# Instruction_Register_Electronic_Scheme_2.net
KiCad netlist of a schematic drawn in Altium Designer
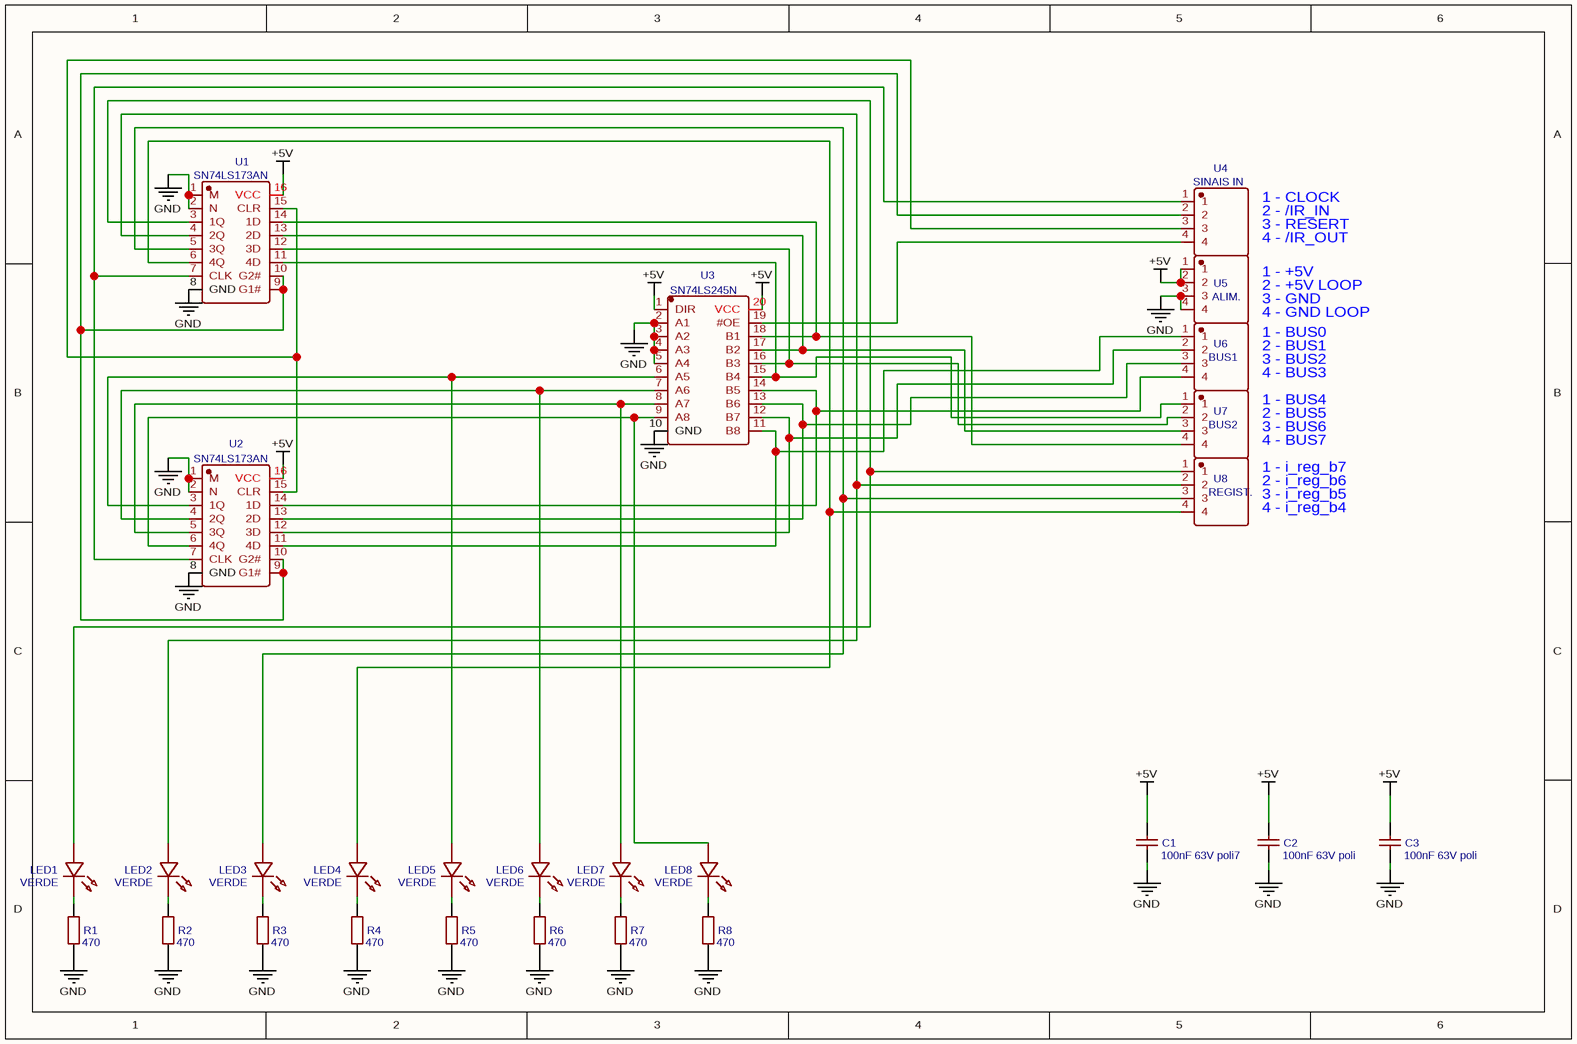
[diagram p0: Instruction Register Electronic Scheme_2021-10-21.schdoc]

(export (version "E")
  (design (tool "Eeschema 10.0.6"))
  (components
    (comp (ref "C1")
      (value "100nF 63V poli7")
      (fields
        (field (name "BOM_SUPPLIER PART") "C444741")
        (field (name "BOM_MANUFACTURER PART") "SR305C105KAR")
        (field (name "CONTRIBUTOR") "LCSC")
      )
      (libsource (lib "altium-import") (part "root_3_100nF 63V poli7_"))
    )
    (comp (ref "C2")
      (value "100nF 63V poli")
      (fields
        (field (name "BOM_SUPPLIER PART") "C444741")
        (field (name "BOM_MANUFACTURER PART") "SR305C105KAR")
        (field (name "CONTRIBUTOR") "LCSC")
      )
      (libsource (lib "altium-import") (part "root_3_100nF 63V poli_"))
    )
    (comp (ref "C3")
      (value "100nF 63V poli")
      (fields
        (field (name "BOM_SUPPLIER PART") "C444741")
        (field (name "BOM_MANUFACTURER PART") "SR305C105KAR")
        (field (name "CONTRIBUTOR") "LCSC")
      )
      (libsource (lib "altium-import") (part "root_3_100nF 63V poli_"))
    )
    (comp (ref "LED1")
      (value "VERDE")
      (fields
        (field (name "BOM_SUPPLIER PART") "C605465")
        (field (name "BOM_MANUFACTURER PART") "264-7GD")
        (field (name "CONTRIBUTOR") "LCSC")
      )
      (libsource (lib "altium-import") (part "root_1_VERDE_"))
    )
    (comp (ref "LED2")
      (value "VERDE")
      (fields
        (field (name "BOM_SUPPLIER PART") "C605465")
        (field (name "BOM_MANUFACTURER PART") "264-7GD")
        (field (name "CONTRIBUTOR") "LCSC")
      )
      (libsource (lib "altium-import") (part "root_1_VERDE_"))
    )
    (comp (ref "LED3")
      (value "VERDE")
      (fields
        (field (name "BOM_SUPPLIER PART") "C605465")
        (field (name "BOM_MANUFACTURER PART") "264-7GD")
        (field (name "CONTRIBUTOR") "LCSC")
      )
      (libsource (lib "altium-import") (part "root_1_VERDE_"))
    )
    (comp (ref "LED4")
      (value "VERDE")
      (fields
        (field (name "BOM_SUPPLIER PART") "C605465")
        (field (name "BOM_MANUFACTURER PART") "264-7GD")
        (field (name "CONTRIBUTOR") "LCSC")
      )
      (libsource (lib "altium-import") (part "root_1_VERDE_"))
    )
    (comp (ref "LED5")
      (value "VERDE")
      (fields
        (field (name "BOM_SUPPLIER PART") "C605465")
        (field (name "BOM_MANUFACTURER PART") "264-7GD")
        (field (name "CONTRIBUTOR") "LCSC")
      )
      (libsource (lib "altium-import") (part "root_1_VERDE_"))
    )
    (comp (ref "LED6")
      (value "VERDE")
      (fields
        (field (name "BOM_SUPPLIER PART") "C605465")
        (field (name "BOM_MANUFACTURER PART") "264-7GD")
        (field (name "CONTRIBUTOR") "LCSC")
      )
      (libsource (lib "altium-import") (part "root_1_VERDE_"))
    )
    (comp (ref "LED7")
      (value "VERDE")
      (fields
        (field (name "BOM_SUPPLIER PART") "C605465")
        (field (name "BOM_MANUFACTURER PART") "264-7GD")
        (field (name "CONTRIBUTOR") "LCSC")
      )
      (libsource (lib "altium-import") (part "root_1_VERDE_"))
    )
    (comp (ref "LED8")
      (value "VERDE")
      (fields
        (field (name "BOM_SUPPLIER PART") "C605465")
        (field (name "BOM_MANUFACTURER PART") "264-7GD")
        (field (name "CONTRIBUTOR") "LCSC")
      )
      (libsource (lib "altium-import") (part "root_1_VERDE_"))
    )
    (comp (ref "R1")
      (value "470")
      (fields
        (field (name "BOM_MANUFACTURER PART") "CFR02SJ0823A10")
        (field (name "BOM_SUPPLIER PART") "C69876")
      )
      (libsource (lib "altium-import") (part "root_3_470_"))
    )
    (comp (ref "R2")
      (value "470")
      (fields
        (field (name "BOM_MANUFACTURER PART") "CFR02SJ0823A10")
        (field (name "BOM_SUPPLIER PART") "C69876")
      )
      (libsource (lib "altium-import") (part "root_3_470_"))
    )
    (comp (ref "R3")
      (value "470")
      (fields
        (field (name "BOM_MANUFACTURER PART") "CFR02SJ0823A10")
        (field (name "BOM_SUPPLIER PART") "C69876")
      )
      (libsource (lib "altium-import") (part "root_3_470_"))
    )
    (comp (ref "R4")
      (value "470")
      (fields
        (field (name "BOM_MANUFACTURER PART") "CFR02SJ0823A10")
        (field (name "BOM_SUPPLIER PART") "C69876")
      )
      (libsource (lib "altium-import") (part "root_3_470_"))
    )
    (comp (ref "R5")
      (value "470")
      (fields
        (field (name "BOM_MANUFACTURER PART") "CFR02SJ0823A10")
        (field (name "BOM_SUPPLIER PART") "C69876")
      )
      (libsource (lib "altium-import") (part "root_3_470_"))
    )
    (comp (ref "R6")
      (value "470")
      (fields
        (field (name "BOM_MANUFACTURER PART") "CFR02SJ0823A10")
        (field (name "BOM_SUPPLIER PART") "C69876")
      )
      (libsource (lib "altium-import") (part "root_3_470_"))
    )
    (comp (ref "R7")
      (value "470")
      (fields
        (field (name "BOM_MANUFACTURER PART") "CFR02SJ0823A10")
        (field (name "BOM_SUPPLIER PART") "C69876")
      )
      (libsource (lib "altium-import") (part "root_3_470_"))
    )
    (comp (ref "R8")
      (value "470")
      (fields
        (field (name "BOM_MANUFACTURER PART") "CFR02SJ0823A10")
        (field (name "BOM_SUPPLIER PART") "C69876")
      )
      (libsource (lib "altium-import") (part "root_3_470_"))
    )
    (comp (ref "U1")
      (value "SN74LS173AN")
      (fields (field (name "BOM_SUPPLIER PART") "C1550125") (field (name "CONTRIBUTOR") "LCSC"))
      (libsource (lib "altium-import") (part "root_0_SN74LS173AN_"))
    )
    (comp (ref "U2")
      (value "SN74LS173AN")
      (fields (field (name "BOM_SUPPLIER PART") "C1550125") (field (name "CONTRIBUTOR") "LCSC"))
      (libsource (lib "altium-import") (part "root_0_SN74LS173AN_"))
    )
    (comp (ref "U3")
      (value "SN74LS245N")
      (fields (field (name "BOM_SUPPLIER PART") "C352966") (field (name "CONTRIBUTOR") "LCSC"))
      (libsource (lib "altium-import") (part "root_0_SN74LS245N_"))
    )
    (comp (ref "U4")
      (value "SINAIS IN")
      (fields
        (field (name "BOM_SUPPLIER PART") "C210162")
        (field (name "BOM_MANUFACTURER PART") "171825-4")
        (field (name "CONTRIBUTOR") "LCSC")
      )
      (libsource (lib "altium-import") (part "root_0_SINAIS IN_"))
    )
    (comp (ref "U5")
      (value "ALIM.")
      (fields
        (field (name "BOM_SUPPLIER PART") "C210162")
        (field (name "BOM_MANUFACTURER PART") "171825-4")
        (field (name "CONTRIBUTOR") "LCSC")
      )
      (libsource (lib "altium-import") (part "root_0_ALIM._"))
    )
    (comp (ref "U6")
      (value "BUS1")
      (fields
        (field (name "BOM_SUPPLIER PART") "C210162")
        (field (name "BOM_MANUFACTURER PART") "171825-4")
        (field (name "CONTRIBUTOR") "LCSC")
      )
      (libsource (lib "altium-import") (part "root_0_BUS1_"))
    )
    (comp (ref "U7")
      (value "BUS2")
      (fields
        (field (name "BOM_SUPPLIER PART") "C210162")
        (field (name "BOM_MANUFACTURER PART") "171825-4")
        (field (name "CONTRIBUTOR") "LCSC")
      )
      (libsource (lib "altium-import") (part "root_0_BUS2_"))
    )
    (comp (ref "U8")
      (value "REGIST.")
      (fields
        (field (name "BOM_SUPPLIER PART") "C210162")
        (field (name "BOM_MANUFACTURER PART") "171825-4")
        (field (name "CONTRIBUTOR") "LCSC")
      )
      (libsource (lib "altium-import") (part "root_0_REGIST._"))
    )
  )
  (nets
    (net (code "1") (name "+5V") (class "Default")
      (node (ref "C1") (pin "1") (pinfunction "1_1") (pintype "passive"))
      (node (ref "C2") (pin "1") (pinfunction "1_1") (pintype "passive"))
      (node (ref "C3") (pin "1") (pinfunction "1_1") (pintype "passive"))
      (node (ref "U1") (pin "16") (pinfunction "VCC_16") (pintype "passive"))
      (node (ref "U2") (pin "16") (pinfunction "VCC_16") (pintype "passive"))
      (node (ref "U3") (pin "1") (pinfunction "DIR_1") (pintype "passive"))
      (node (ref "U3") (pin "20") (pinfunction "VCC_20") (pintype "passive"))
      (node (ref "U5") (pin "1") (pinfunction "1_1") (pintype "passive"))
      (node (ref "U5") (pin "2") (pinfunction "2_2") (pintype "passive"))
    )
    (net (code "2") (name "GND") (class "Default")
      (node (ref "C1") (pin "2") (pinfunction "2_2") (pintype "passive"))
      (node (ref "C2") (pin "2") (pinfunction "2_2") (pintype "passive"))
      (node (ref "C3") (pin "2") (pinfunction "2_2") (pintype "passive"))
      (node (ref "R1") (pin "2") (pinfunction "2_2") (pintype "passive"))
      (node (ref "R2") (pin "2") (pinfunction "2_2") (pintype "passive"))
      (node (ref "R3") (pin "2") (pinfunction "2_2") (pintype "passive"))
      (node (ref "R4") (pin "2") (pinfunction "2_2") (pintype "passive"))
      (node (ref "R5") (pin "2") (pinfunction "2_2") (pintype "passive"))
      (node (ref "R6") (pin "2") (pinfunction "2_2") (pintype "passive"))
      (node (ref "R7") (pin "2") (pinfunction "2_2") (pintype "passive"))
      (node (ref "R8") (pin "2") (pinfunction "2_2") (pintype "passive"))
      (node (ref "U1") (pin "1") (pinfunction "M_1") (pintype "passive"))
      (node (ref "U1") (pin "2") (pinfunction "N_2") (pintype "passive"))
      (node (ref "U1") (pin "8") (pinfunction "GND_8") (pintype "passive"))
      (node (ref "U2") (pin "1") (pinfunction "M_1") (pintype "passive"))
      (node (ref "U2") (pin "2") (pinfunction "N_2") (pintype "passive"))
      (node (ref "U2") (pin "8") (pinfunction "GND_8") (pintype "passive"))
      (node (ref "U3") (pin "10") (pinfunction "GND_10") (pintype "passive"))
      (node (ref "U3") (pin "2") (pinfunction "A1_2") (pintype "passive"))
      (node (ref "U3") (pin "3") (pinfunction "A2_3") (pintype "passive"))
      (node (ref "U3") (pin "4") (pinfunction "A3_4") (pintype "passive"))
      (node (ref "U3") (pin "5") (pinfunction "A4_5") (pintype "passive"))
      (node (ref "U5") (pin "3") (pinfunction "3_3") (pintype "passive"))
      (node (ref "U5") (pin "4") (pinfunction "4_4") (pintype "passive"))
    )
    (net (code "3") (name "Net-(LED1-+)") (class "Default")
      (node (ref "LED1") (pin "2") (pinfunction "+_2") (pintype "passive"))
      (node (ref "U1") (pin "3") (pinfunction "1Q_3") (pintype "passive"))
      (node (ref "U8") (pin "1") (pinfunction "1_1") (pintype "passive"))
    )
    (net (code "4") (name "Net-(LED1--)") (class "Default")
      (node (ref "LED1") (pin "1") (pinfunction "-_1") (pintype "passive"))
      (node (ref "R1") (pin "1") (pinfunction "1_1") (pintype "passive"))
    )
    (net (code "5") (name "Net-(LED2-+)") (class "Default")
      (node (ref "LED2") (pin "2") (pinfunction "+_2") (pintype "passive"))
      (node (ref "U1") (pin "4") (pinfunction "2Q_4") (pintype "passive"))
      (node (ref "U8") (pin "2") (pinfunction "2_2") (pintype "passive"))
    )
    (net (code "6") (name "Net-(LED2--)") (class "Default")
      (node (ref "LED2") (pin "1") (pinfunction "-_1") (pintype "passive"))
      (node (ref "R2") (pin "1") (pinfunction "1_1") (pintype "passive"))
    )
    (net (code "7") (name "Net-(LED3-+)") (class "Default")
      (node (ref "LED3") (pin "2") (pinfunction "+_2") (pintype "passive"))
      (node (ref "U1") (pin "5") (pinfunction "3Q_5") (pintype "passive"))
      (node (ref "U8") (pin "3") (pinfunction "3_3") (pintype "passive"))
    )
    (net (code "8") (name "Net-(LED3--)") (class "Default")
      (node (ref "LED3") (pin "1") (pinfunction "-_1") (pintype "passive"))
      (node (ref "R3") (pin "1") (pinfunction "1_1") (pintype "passive"))
    )
    (net (code "9") (name "Net-(LED4-+)") (class "Default")
      (node (ref "LED4") (pin "2") (pinfunction "+_2") (pintype "passive"))
      (node (ref "U1") (pin "6") (pinfunction "4Q_6") (pintype "passive"))
      (node (ref "U8") (pin "4") (pinfunction "4_4") (pintype "passive"))
    )
    (net (code "10") (name "Net-(LED4--)") (class "Default")
      (node (ref "LED4") (pin "1") (pinfunction "-_1") (pintype "passive"))
      (node (ref "R4") (pin "1") (pinfunction "1_1") (pintype "passive"))
    )
    (net (code "11") (name "Net-(LED5-+)") (class "Default")
      (node (ref "LED5") (pin "2") (pinfunction "+_2") (pintype "passive"))
      (node (ref "U2") (pin "3") (pinfunction "1Q_3") (pintype "passive"))
      (node (ref "U3") (pin "6") (pinfunction "A5_6") (pintype "passive"))
    )
    (net (code "12") (name "Net-(LED5--)") (class "Default")
      (node (ref "LED5") (pin "1") (pinfunction "-_1") (pintype "passive"))
      (node (ref "R5") (pin "1") (pinfunction "1_1") (pintype "passive"))
    )
    (net (code "13") (name "Net-(LED6-+)") (class "Default")
      (node (ref "LED6") (pin "2") (pinfunction "+_2") (pintype "passive"))
      (node (ref "U2") (pin "4") (pinfunction "2Q_4") (pintype "passive"))
      (node (ref "U3") (pin "7") (pinfunction "A6_7") (pintype "passive"))
    )
    (net (code "14") (name "Net-(LED6--)") (class "Default")
      (node (ref "LED6") (pin "1") (pinfunction "-_1") (pintype "passive"))
      (node (ref "R6") (pin "1") (pinfunction "1_1") (pintype "passive"))
    )
    (net (code "15") (name "Net-(LED7-+)") (class "Default")
      (node (ref "LED7") (pin "2") (pinfunction "+_2") (pintype "passive"))
      (node (ref "U2") (pin "5") (pinfunction "3Q_5") (pintype "passive"))
      (node (ref "U3") (pin "8") (pinfunction "A7_8") (pintype "passive"))
    )
    (net (code "16") (name "Net-(LED7--)") (class "Default")
      (node (ref "LED7") (pin "1") (pinfunction "-_1") (pintype "passive"))
      (node (ref "R7") (pin "1") (pinfunction "1_1") (pintype "passive"))
    )
    (net (code "17") (name "Net-(LED8-+)") (class "Default")
      (node (ref "LED8") (pin "2") (pinfunction "+_2") (pintype "passive"))
      (node (ref "U2") (pin "6") (pinfunction "4Q_6") (pintype "passive"))
      (node (ref "U3") (pin "9") (pinfunction "A8_9") (pintype "passive"))
    )
    (net (code "18") (name "Net-(LED8--)") (class "Default")
      (node (ref "LED8") (pin "1") (pinfunction "-_1") (pintype "passive"))
      (node (ref "R8") (pin "1") (pinfunction "1_1") (pintype "passive"))
    )
    (net (code "19") (name "Net-(U1-1D)") (class "Default")
      (node (ref "U1") (pin "14") (pinfunction "1D_14") (pintype "passive"))
      (node (ref "U3") (pin "18") (pinfunction "B1_18") (pintype "passive"))
      (node (ref "U7") (pin "4") (pinfunction "4_4") (pintype "passive"))
    )
    (net (code "20") (name "Net-(U1-2D)") (class "Default")
      (node (ref "U1") (pin "13") (pinfunction "2D_13") (pintype "passive"))
      (node (ref "U3") (pin "17") (pinfunction "B2_17") (pintype "passive"))
      (node (ref "U7") (pin "3") (pinfunction "3_3") (pintype "passive"))
    )
    (net (code "21") (name "Net-(U1-3D)") (class "Default")
      (node (ref "U1") (pin "12") (pinfunction "3D_12") (pintype "passive"))
      (node (ref "U3") (pin "16") (pinfunction "B3_16") (pintype "passive"))
      (node (ref "U7") (pin "2") (pinfunction "2_2") (pintype "passive"))
    )
    (net (code "22") (name "Net-(U1-4D)") (class "Default")
      (node (ref "U1") (pin "11") (pinfunction "4D_11") (pintype "passive"))
      (node (ref "U3") (pin "15") (pinfunction "B4_15") (pintype "passive"))
      (node (ref "U7") (pin "1") (pinfunction "1_1") (pintype "passive"))
    )
    (net (code "23") (name "Net-(U1-CLK)") (class "Default")
      (node (ref "U1") (pin "7") (pinfunction "CLK_7") (pintype "passive"))
      (node (ref "U2") (pin "7") (pinfunction "CLK_7") (pintype "passive"))
      (node (ref "U4") (pin "1") (pinfunction "1_1") (pintype "passive"))
    )
    (net (code "24") (name "Net-(U1-CLR)") (class "Default")
      (node (ref "U1") (pin "15") (pinfunction "CLR_15") (pintype "passive"))
      (node (ref "U2") (pin "15") (pinfunction "CLR_15") (pintype "passive"))
      (node (ref "U4") (pin "3") (pinfunction "3_3") (pintype "passive"))
    )
    (net (code "25") (name "Net-(U1-G1#)") (class "Default")
      (node (ref "U1") (pin "10") (pinfunction "G2#_10") (pintype "passive"))
      (node (ref "U1") (pin "9") (pinfunction "G1#_9") (pintype "passive"))
      (node (ref "U2") (pin "10") (pinfunction "G2#_10") (pintype "passive"))
      (node (ref "U2") (pin "9") (pinfunction "G1#_9") (pintype "passive"))
      (node (ref "U4") (pin "2") (pinfunction "2_2") (pintype "passive"))
    )
    (net (code "26") (name "Net-(U2-1D)") (class "Default")
      (node (ref "U2") (pin "14") (pinfunction "1D_14") (pintype "passive"))
      (node (ref "U3") (pin "14") (pinfunction "B5_14") (pintype "passive"))
      (node (ref "U6") (pin "4") (pinfunction "4_4") (pintype "passive"))
    )
    (net (code "27") (name "Net-(U2-2D)") (class "Default")
      (node (ref "U2") (pin "13") (pinfunction "2D_13") (pintype "passive"))
      (node (ref "U3") (pin "13") (pinfunction "B6_13") (pintype "passive"))
      (node (ref "U6") (pin "3") (pinfunction "3_3") (pintype "passive"))
    )
    (net (code "28") (name "Net-(U2-3D)") (class "Default")
      (node (ref "U2") (pin "12") (pinfunction "3D_12") (pintype "passive"))
      (node (ref "U3") (pin "12") (pinfunction "B7_12") (pintype "passive"))
      (node (ref "U6") (pin "2") (pinfunction "2_2") (pintype "passive"))
    )
    (net (code "29") (name "Net-(U2-4D)") (class "Default")
      (node (ref "U2") (pin "11") (pinfunction "4D_11") (pintype "passive"))
      (node (ref "U3") (pin "11") (pinfunction "B8_11") (pintype "passive"))
      (node (ref "U6") (pin "1") (pinfunction "1_1") (pintype "passive"))
    )
    (net (code "30") (name "Net-(U3-#OE)") (class "Default")
      (node (ref "U3") (pin "19") (pinfunction "#OE_19") (pintype "passive"))
      (node (ref "U4") (pin "4") (pinfunction "4_4") (pintype "passive"))
    )
  )
)
